# 3_-RK3399_EMMC_ADC_PCIE.net
KiCad netlist of a schematic drawn in Altium Designer
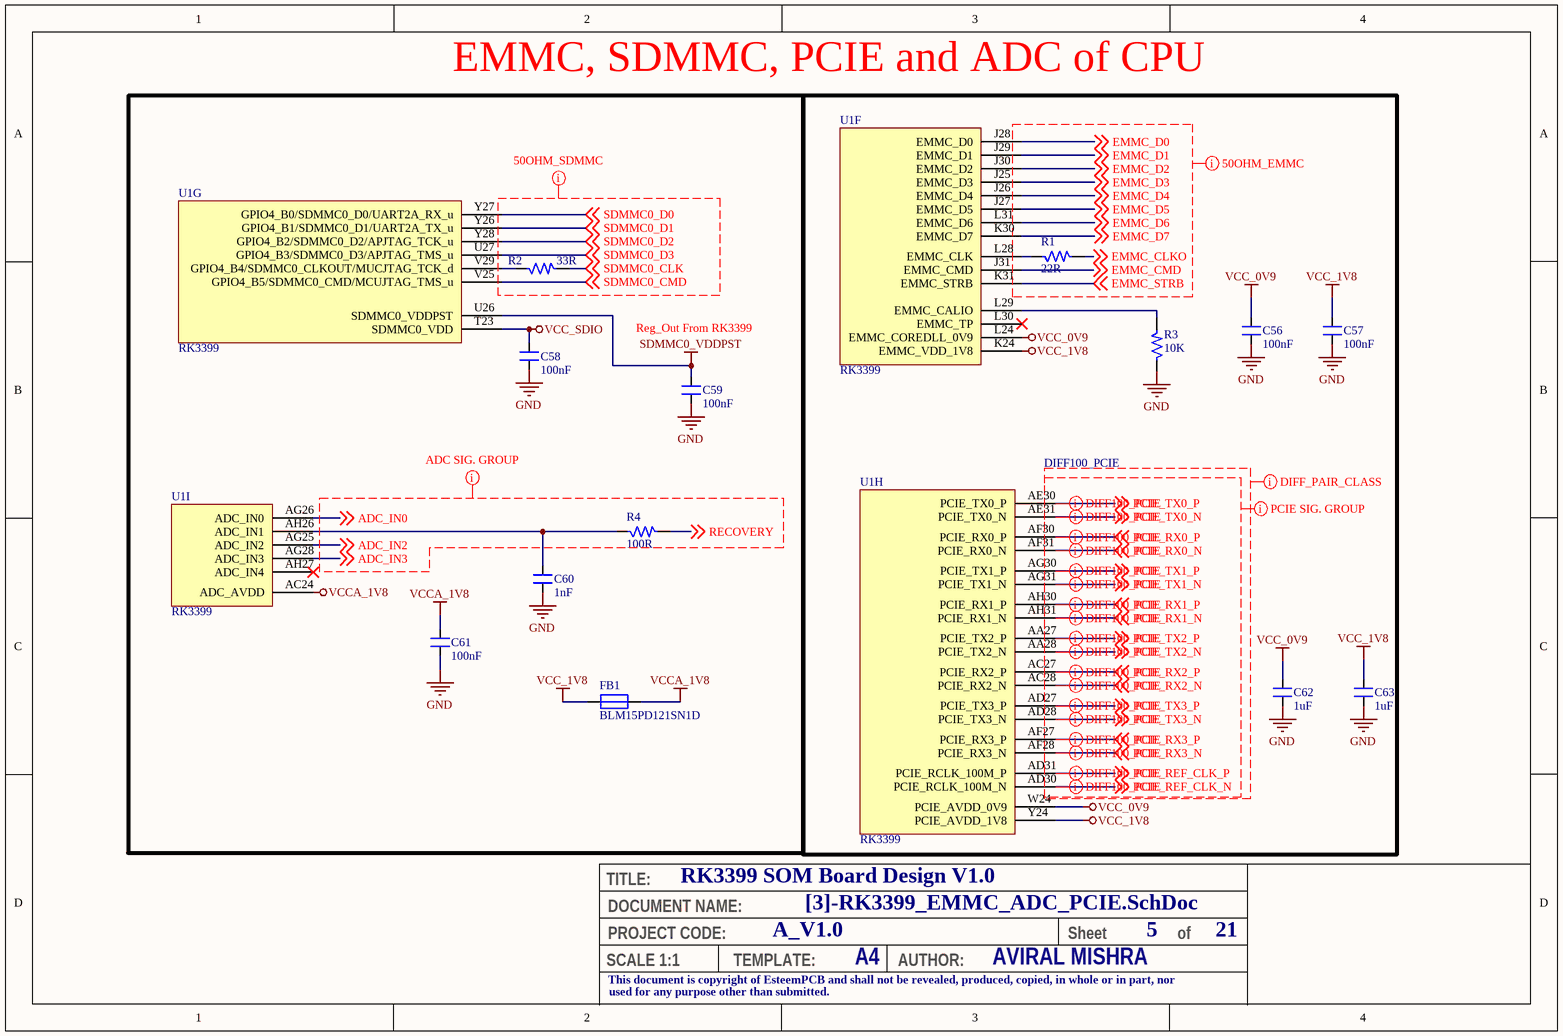
[diagram p0: [3]-RK3399_EMMC_ADC_PCIE.SchDoc]

(export (version "E")
  (design (tool "Eeschema 10.0.6"))
  (components
    (comp (ref "C56")
      (value "100nF")
      (footprint "CAP_0201")
      (description "0.1µF ±10% 25V Ceramic Capacitor X5R 0201 (0603 Metric)")
      (fields
        (field (name "MANUFACTURER") "TDK Corporation")
        (field (name "MANUFACTURER PART NUMBER") "C0603X5R1E104K030BB")
      )
      (libsource (lib "RK3399 _Module_Intlib") (part "CAP_100nF-25V-10%-0201"))
    )
    (comp (ref "C57")
      (value "100nF")
      (footprint "CAP_0201")
      (description "0.1µF ±10% 25V Ceramic Capacitor X5R 0201 (0603 Metric)")
      (fields
        (field (name "MANUFACTURER") "TDK Corporation")
        (field (name "MANUFACTURER PART NUMBER") "C0603X5R1E104K030BB")
      )
      (libsource (lib "RK3399 _Module_Intlib") (part "CAP_100nF-25V-10%-0201"))
    )
    (comp (ref "C58")
      (value "100nF")
      (footprint "CAP_0201")
      (description "0.1µF ±10% 25V Ceramic Capacitor X5R 0201 (0603 Metric)")
      (fields
        (field (name "MANUFACTURER") "TDK Corporation")
        (field (name "MANUFACTURER PART NUMBER") "C0603X5R1E104K030BB")
      )
      (libsource (lib "RK3399 _Module_Intlib") (part "CAP_100nF-25V-10%-0201"))
    )
    (comp (ref "C59")
      (value "100nF")
      (footprint "CAP_0201")
      (description "0.1µF ±10% 25V Ceramic Capacitor X5R 0201 (0603 Metric)")
      (fields
        (field (name "MANUFACTURER") "TDK Corporation")
        (field (name "MANUFACTURER PART NUMBER") "C0603X5R1E104K030BB")
      )
      (libsource (lib "RK3399 _Module_Intlib") (part "CAP_100nF-25V-10%-0201"))
    )
    (comp (ref "C60")
      (value "1nF")
      (footprint "CAP_0201")
      (description "1000pF ±10% 16V Ceramic Capacitor X7R 0201 (0603 Metric)")
      (fields
        (field (name "MANUFACTURER") "Murata Electronics")
        (field (name "MANUFACTURER PART NUMBER") "GRM033R71C102KA01D")
      )
      (libsource (lib "RK3399 _Module_Intlib") (part "CAP_1nF-16V-10%-0201"))
    )
    (comp (ref "C61")
      (value "100nF")
      (footprint "CAP_0201")
      (description "0.1µF ±10% 25V Ceramic Capacitor X5R 0201 (0603 Metric)")
      (fields
        (field (name "MANUFACTURER") "TDK Corporation")
        (field (name "MANUFACTURER PART NUMBER") "C0603X5R1E104K030BB")
      )
      (libsource (lib "RK3399 _Module_Intlib") (part "CAP_100nF-25V-10%-0201"))
    )
    (comp (ref "C62")
      (value "1uF")
      (footprint "CAP_0201")
      (description "1µF ±20% 16V Ceramic Capacitor X5R 0201 (0603 Metric)")
      (fields
        (field (name "MANUFACTURER") "Samsung Electro-Mechanics")
        (field (name "MANUFACTURER PART NUMBER") "CL03A105MO3NRNH")
      )
      (libsource (lib "RK3399 _Module_Intlib") (part "CAP_1uF-16V-10%-0201"))
    )
    (comp (ref "C63")
      (value "1uF")
      (footprint "CAP_0201")
      (description "1µF ±20% 16V Ceramic Capacitor X5R 0201 (0603 Metric)")
      (fields
        (field (name "MANUFACTURER") "Samsung Electro-Mechanics")
        (field (name "MANUFACTURER PART NUMBER") "CL03A105MO3NRNH")
      )
      (libsource (lib "RK3399 _Module_Intlib") (part "CAP_1uF-16V-10%-0201"))
    )
    (comp (ref "FB1")
      (value "BLM15PD121SN1D")
      (footprint "RES_0402")
      (description "120 Ohms @ 100MHz 1 Power Line Ferrite Bead 0402 (1005 Metric) 1.3A 90mOhm")
      (fields (field (name "MANUFACTURER") "Murata Electronics"))
      (libsource (lib "RK3399 _Module_Schlib") (part "FB_120R-1.3A-100Mhz-0402"))
    )
    (comp (ref "R1")
      (value "22R")
      (footprint "RES_0201")
      (description "22 Ohms ±1% 0.05W, 1/20W Chip Resistor 0201 (0603 Metric) Moisture Resistant Thick Film")
      (fields
        (field (name "MANUFACTURER") "Yageo")
        (field (name "MANUFACTURER PART NUMBER") "RC0201FR-0722RL")
      )
      (libsource (lib "EsteemPCB_SOM_Course_schlib") (part "RES_22R-0.05W-1%-0201"))
    )
    (comp (ref "R2")
      (value "33R")
      (footprint "RES_0201")
      (description "33 Ohms ±1% 0.05W, 1/20W Chip Resistor 0201 (0603 Metric) Thick Film")
      (fields
        (field (name "MANUFACTURER") "Yageo")
        (field (name "MANUFACTURER PART NUMBER") "RC0201FR-0733RL")
      )
      (libsource (lib "RK3399 _Module_Intlib") (part "RES_33R-0.05W-1%-0201"))
    )
    (comp (ref "R3")
      (value "10K")
      (footprint "RES_0201")
      (description "10 kOhms ±1% 0.05W, 1/20W Chip Resistor 0201 (0603 Metric) Thick Film")
      (fields
        (field (name "MANUFACTURER") "Stackpole Electronics Inc")
        (field (name "MANUFACTURER PART NUMBER") "RMCF0201FT10K0")
      )
      (libsource (lib "RK3399 _Module_Intlib") (part "RES_10K-0.05W-1%-0201"))
    )
    (comp (ref "R4")
      (value "100R")
      (footprint "RES_0201")
      (description "100 kOhms ±1% 0.05W, 1/20W Chip Resistor 0201 (0603 Metric) Automotive AEC-Q200 Thick Film")
      (fields
        (field (name "MANUFACTURER") "Panasonic Electronic Components")
        (field (name "MANUFACTURER PART NUMBER") "ERJ-1GNF1003C")
      )
      (libsource (lib "RK3399 _Module_Intlib") (part "RES_100R-0.05W-1%-0201"))
    )
    (comp (ref "U1")
      (value "RK3399")
      (footprint "FBGA828_23_826X826")
      (description "RK3399 is a low power, high performance processor for computing, personal mobile.")
      (fields (field (name "MANUFACTURER") "Rockchip"))
      (libsource (lib "RK3399 _Module_Schlib") (part "IC_RK3399-FCBGA828"))
    )
  )
  (nets
    (net (code "1") (name "ADC_IN0") (class "Default")
      (node (ref "U1") (pin "AG26") (pinfunction "ADC_IN0_AG26") (pintype "passive"))
    )
    (net (code "2") (name "ADC_IN2") (class "Default")
      (node (ref "U1") (pin "AG25") (pinfunction "ADC_IN2_AG25") (pintype "passive"))
    )
    (net (code "3") (name "ADC_IN3") (class "Default")
      (node (ref "U1") (pin "AG28") (pinfunction "ADC_IN3_AG28") (pintype "passive"))
    )
    (net (code "4") (name "EMMC_CLKO") (class "Default")
      (node (ref "R1") (pin "2") (pinfunction "2_2") (pintype "passive"))
    )
    (net (code "5") (name "EMMC_CMD") (class "Default")
      (node (ref "U1") (pin "J31") (pinfunction "EMMC_CMD_J31") (pintype "passive"))
    )
    (net (code "6") (name "EMMC_D0") (class "Default")
      (node (ref "U1") (pin "J28") (pinfunction "EMMC_D0_J28") (pintype "passive"))
    )
    (net (code "7") (name "EMMC_D1") (class "Default")
      (node (ref "U1") (pin "J29") (pinfunction "EMMC_D1_J29") (pintype "passive"))
    )
    (net (code "8") (name "EMMC_D2") (class "Default")
      (node (ref "U1") (pin "J30") (pinfunction "EMMC_D2_J30") (pintype "passive"))
    )
    (net (code "9") (name "EMMC_D3") (class "Default")
      (node (ref "U1") (pin "J25") (pinfunction "EMMC_D3_J25") (pintype "passive"))
    )
    (net (code "10") (name "EMMC_D4") (class "Default")
      (node (ref "U1") (pin "J26") (pinfunction "EMMC_D4_J26") (pintype "passive"))
    )
    (net (code "11") (name "EMMC_D5") (class "Default")
      (node (ref "U1") (pin "J27") (pinfunction "EMMC_D5_J27") (pintype "passive"))
    )
    (net (code "12") (name "EMMC_D6") (class "Default")
      (node (ref "U1") (pin "L31") (pinfunction "EMMC_D6_L31") (pintype "passive"))
    )
    (net (code "13") (name "EMMC_D7") (class "Default")
      (node (ref "U1") (pin "K30") (pinfunction "EMMC_D7_K30") (pintype "passive"))
    )
    (net (code "14") (name "EMMC_STRB") (class "Default")
      (node (ref "U1") (pin "K31") (pinfunction "EMMC_STRB_K31") (pintype "passive"))
    )
    (net (code "15") (name "GND") (class "Default")
      (node (ref "C56") (pin "1") (pinfunction "1_1") (pintype "passive"))
      (node (ref "C57") (pin "1") (pinfunction "1_1") (pintype "passive"))
      (node (ref "C58") (pin "1") (pinfunction "1_1") (pintype "passive"))
      (node (ref "C59") (pin "1") (pinfunction "1_1") (pintype "passive"))
      (node (ref "C60") (pin "1") (pinfunction "1_1") (pintype "passive"))
      (node (ref "C61") (pin "1") (pinfunction "1_1") (pintype "passive"))
      (node (ref "C62") (pin "1") (pinfunction "1_1") (pintype "passive"))
      (node (ref "C63") (pin "1") (pinfunction "1_1") (pintype "passive"))
      (node (ref "R3") (pin "1") (pinfunction "1_1") (pintype "passive"))
    )
    (net (code "16") (name "Net-(U1F-EMMC_CALIO)") (class "Default")
      (node (ref "R3") (pin "2") (pinfunction "2_2") (pintype "passive"))
      (node (ref "U1") (pin "L29") (pinfunction "EMMC_CALIO_L29") (pintype "passive"))
    )
    (net (code "17") (name "Net-(U1F-EMMC_CLK)") (class "Default")
      (node (ref "R1") (pin "1") (pinfunction "1_1") (pintype "passive"))
      (node (ref "U1") (pin "L28") (pinfunction "EMMC_CLK_L28") (pintype "passive"))
    )
    (net (code "18") (name "Net-(U1G-GPIO4_B4{slash}SDMMC0_CLKOUT{slash}MUCJTAG_TCK_d)") (class "Default")
      (node (ref "R2") (pin "1") (pinfunction "1_1") (pintype "passive"))
      (node (ref "U1") (pin "V29") (pinfunction "GPIO4_B4/SDMMC0_CLKOUT/MUCJTAG_TCK_d_V29") (pintype "passive"))
    )
    (net (code "19") (name "Net-(U1I-ADC_IN1)") (class "Default")
      (node (ref "C60") (pin "2") (pinfunction "2_2") (pintype "passive"))
      (node (ref "R4") (pin "1") (pinfunction "1_1") (pintype "passive"))
      (node (ref "U1") (pin "AH26") (pinfunction "ADC_IN1_AH26") (pintype "passive"))
    )
    (net (code "20") (name "PCIE_REF_CLK_N") (class "Default")
      (node (ref "U1") (pin "AD30") (pinfunction "PCIE_RCLK_100M_N_AD30") (pintype "passive"))
    )
    (net (code "21") (name "PCIE_REF_CLK_P") (class "Default")
      (node (ref "U1") (pin "AD31") (pinfunction "PCIE_RCLK_100M_P_AD31") (pintype "passive"))
    )
    (net (code "22") (name "PCIE_RX0_N") (class "Default")
      (node (ref "U1") (pin "AF31") (pinfunction "PCIE_RX0_N_AF31") (pintype "passive"))
    )
    (net (code "23") (name "PCIE_RX0_P") (class "Default")
      (node (ref "U1") (pin "AF30") (pinfunction "PCIE_RX0_P_AF30") (pintype "passive"))
    )
    (net (code "24") (name "PCIE_RX1_N") (class "Default")
      (node (ref "U1") (pin "AH31") (pinfunction "PCIE_RX1_N_AH31") (pintype "passive"))
    )
    (net (code "25") (name "PCIE_RX1_P") (class "Default")
      (node (ref "U1") (pin "AH30") (pinfunction "PCIE_RX1_P_AH30") (pintype "passive"))
    )
    (net (code "26") (name "PCIE_RX2_N") (class "Default")
      (node (ref "U1") (pin "AC28") (pinfunction "PCIE_RX2_N_AC28") (pintype "passive"))
    )
    (net (code "27") (name "PCIE_RX2_P") (class "Default")
      (node (ref "U1") (pin "AC27") (pinfunction "PCIE_RX2_P_AC27") (pintype "passive"))
    )
    (net (code "28") (name "PCIE_RX3_N") (class "Default")
      (node (ref "U1") (pin "AF28") (pinfunction "PCIE_RX3_N_AF28") (pintype "passive"))
    )
    (net (code "29") (name "PCIE_RX3_P") (class "Default")
      (node (ref "U1") (pin "AF27") (pinfunction "PCIE_RX3_P_AF27") (pintype "passive"))
    )
    (net (code "30") (name "PCIE_TX0_N") (class "Default")
      (node (ref "U1") (pin "AE31") (pinfunction "PCIE_TX0_N_AE31") (pintype "passive"))
    )
    (net (code "31") (name "PCIE_TX0_P") (class "Default")
      (node (ref "U1") (pin "AE30") (pinfunction "PCIE_TX0_P_AE30") (pintype "passive"))
    )
    (net (code "32") (name "PCIE_TX1_N") (class "Default")
      (node (ref "U1") (pin "AG31") (pinfunction "PCIE_TX1_N_AG31") (pintype "passive"))
    )
    (net (code "33") (name "PCIE_TX1_P") (class "Default")
      (node (ref "U1") (pin "AG30") (pinfunction "PCIE_TX1_P_AG30") (pintype "passive"))
    )
    (net (code "34") (name "PCIE_TX2_N") (class "Default")
      (node (ref "U1") (pin "AA28") (pinfunction "PCIE_TX2_N_AA28") (pintype "passive"))
    )
    (net (code "35") (name "PCIE_TX2_P") (class "Default")
      (node (ref "U1") (pin "AA27") (pinfunction "PCIE_TX2_P_AA27") (pintype "passive"))
    )
    (net (code "36") (name "PCIE_TX3_N") (class "Default")
      (node (ref "U1") (pin "AD28") (pinfunction "PCIE_TX3_N_AD28") (pintype "passive"))
    )
    (net (code "37") (name "PCIE_TX3_P") (class "Default")
      (node (ref "U1") (pin "AD27") (pinfunction "PCIE_TX3_P_AD27") (pintype "passive"))
    )
    (net (code "38") (name "RECOVERY") (class "Default")
      (node (ref "R4") (pin "2") (pinfunction "2_2") (pintype "passive"))
    )
    (net (code "39") (name "SDMMC0_CLK") (class "Default")
      (node (ref "R2") (pin "2") (pinfunction "2_2") (pintype "passive"))
    )
    (net (code "40") (name "SDMMC0_CMD") (class "Default")
      (node (ref "U1") (pin "V25") (pinfunction "GPIO4_B5/SDMMC0_CMD/MCUJTAG_TMS_u_V25") (pintype "passive"))
    )
    (net (code "41") (name "SDMMC0_D0") (class "Default")
      (node (ref "U1") (pin "Y27") (pinfunction "GPIO4_B0/SDMMC0_D0/UART2A_RX_u_Y27") (pintype "passive"))
    )
    (net (code "42") (name "SDMMC0_D1") (class "Default")
      (node (ref "U1") (pin "Y26") (pinfunction "GPIO4_B1/SDMMC0_D1/UART2A_TX_u_Y26") (pintype "passive"))
    )
    (net (code "43") (name "SDMMC0_D2") (class "Default")
      (node (ref "U1") (pin "Y28") (pinfunction "GPIO4_B2/SDMMC0_D2/APJTAG_TCK_u_Y28") (pintype "passive"))
    )
    (net (code "44") (name "SDMMC0_D3") (class "Default")
      (node (ref "U1") (pin "U27") (pinfunction "GPIO4_B3/SDMMC0_D3/APJTAG_TMS_u_U27") (pintype "passive"))
    )
    (net (code "45") (name "SDMMC0_VDDPST") (class "Default")
      (node (ref "C59") (pin "2") (pinfunction "2_2") (pintype "passive"))
      (node (ref "U1") (pin "U26") (pinfunction "SDMMC0_VDDPST_U26") (pintype "passive"))
    )
    (net (code "46") (name "VCCA_1V8") (class "Default")
      (node (ref "C61") (pin "2") (pinfunction "2_2") (pintype "passive"))
      (node (ref "FB1") (pin "2") (pinfunction "2_2") (pintype "passive"))
      (node (ref "U1") (pin "AC24") (pinfunction "ADC_AVDD_AC24") (pintype "passive"))
    )
    (net (code "47") (name "VCC_0V9") (class "Default")
      (node (ref "C56") (pin "2") (pinfunction "2_2") (pintype "passive"))
      (node (ref "C62") (pin "2") (pinfunction "2_2") (pintype "passive"))
      (node (ref "U1") (pin "L24") (pinfunction "EMMC_COREDLL_0V9_L24") (pintype "passive"))
      (node (ref "U1") (pin "W24") (pinfunction "PCIE_AVDD_0V9_W24") (pintype "passive"))
    )
    (net (code "48") (name "VCC_1V8") (class "Default")
      (node (ref "C57") (pin "2") (pinfunction "2_2") (pintype "passive"))
      (node (ref "C63") (pin "2") (pinfunction "2_2") (pintype "passive"))
      (node (ref "FB1") (pin "1") (pinfunction "1_1") (pintype "passive"))
      (node (ref "U1") (pin "K24") (pinfunction "EMMC_VDD_1V8_K24") (pintype "passive"))
      (node (ref "U1") (pin "Y24") (pinfunction "PCIE_AVDD_1V8_Y24") (pintype "passive"))
    )
    (net (code "49") (name "VCC_SDIO") (class "Default")
      (node (ref "C58") (pin "2") (pinfunction "2_2") (pintype "passive"))
      (node (ref "U1") (pin "T23") (pinfunction "SDMMC0_VDD_T23") (pintype "passive"))
    )
    (net (code "50") (name "unconnected-(U1F-EMMC_TP-PadL30)") (class "Default")
      (node (ref "U1") (pin "L30") (pinfunction "EMMC_TP_L30") (pintype "passive+no_connect"))
    )
    (net (code "51") (name "unconnected-(U1I-ADC_IN4-PadAH27)") (class "Default")
      (node (ref "U1") (pin "AH27") (pinfunction "ADC_IN4_AH27") (pintype "passive+no_connect"))
    )
  )
)
